# APM9328_PERIPH.net
KiCad netlist of a schematic drawn in Altium Designer
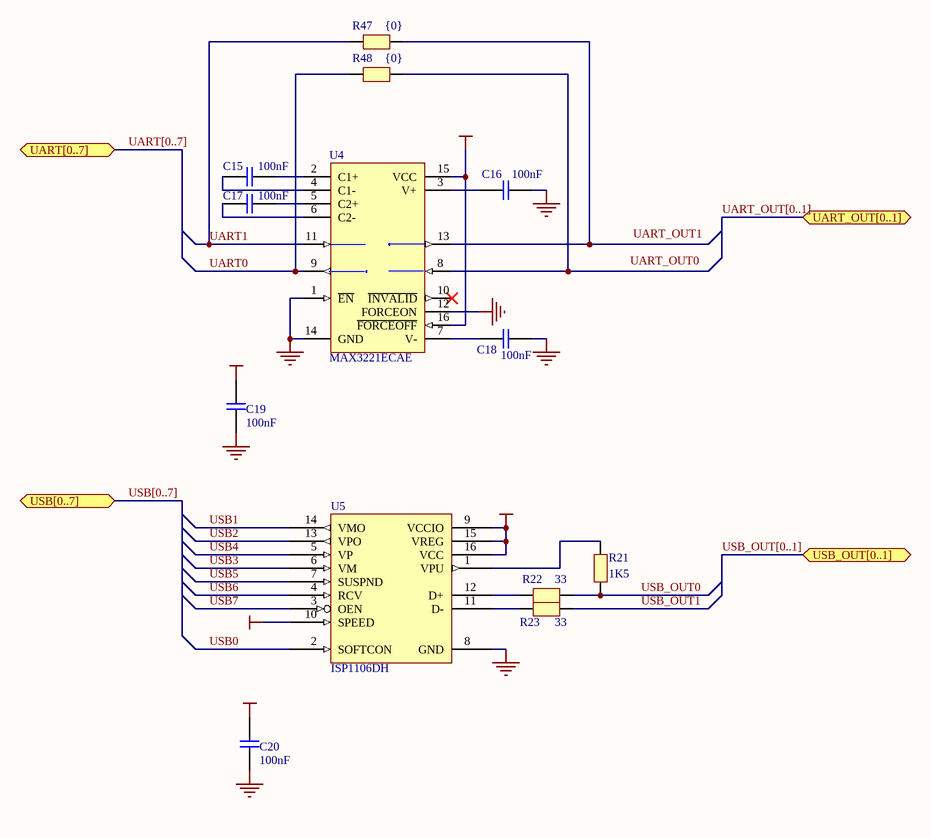
[diagram p0: APM9328_PERIPH.SchDoc]

(export (version "E")
  (design (tool "Eeschema 10.0.6"))
  (components
    (comp (ref "C15") (value "100nF") (footprint "0402") (libsource (lib "Misc") (part "Cap")))
    (comp (ref "C16") (value "100nF") (footprint "0402") (libsource (lib "Misc") (part "Cap")))
    (comp (ref "C17") (value "100nF") (footprint "0402") (libsource (lib "Misc") (part "Cap")))
    (comp (ref "C18") (value "100nF") (footprint "0402") (libsource (lib "Misc") (part "Cap")))
    (comp (ref "C19") (value "100nF") (footprint "0402") (libsource (lib "Misc") (part "Cap")))
    (comp (ref "C20") (value "100nF") (footprint "0402") (libsource (lib "Misc") (part "Cap")))
    (comp (ref "R21") (value "1K5") (footprint "0402") (libsource (lib "") (part "Res_1")))
    (comp (ref "R22") (value "33") (footprint "0402") (libsource (lib "*") (part "Res")))
    (comp (ref "R23") (value "33") (footprint "0402") (libsource (lib "*") (part "Res")))
    (comp (ref "R47") (value "{0}") (footprint "0402") (libsource (lib "*") (part "Res")))
    (comp (ref "R48") (value "{0}") (footprint "0402") (libsource (lib "*") (part "Res")))
    (comp (ref "U4")
      (value "MAX3221ECAE")
      (footprint "TSSOP16")
      (description "±15kV ESD-Protected, 1µA, 3.0V/5.5V, 250kbps, RS-232 Transceiver with AutoShutdown")
      (fields
        (field (name "MANUFACTURER") "Texas Instrument")
        (field (name "PART NUMBER") "MAX3221CPWR")
        (field (name "PUBLISHER") "Altium Limited")
      )
      (libsource (lib "Maxim Communication Transceiver") (part "MAX3221ECAE"))
    )
    (comp (ref "U5")
      (value "ISP1106DH")
      (footprint "TSSOP16")
      (description "USB 1.1 transceiver")
      (fields (field (name "MANUFACTURER") "Philips"))
      (libsource (lib "*") (part "ISP1106"))
    )
  )
  (nets
    (net (code "7") (name "+3V3") (class "Default")
      (node (ref "C19") (pin "1") (pintype "passive"))
      (node (ref "C20") (pin "1") (pintype "passive"))
      (node (ref "U4") (pin "15") (pinfunction "VCC_15") (pintype "power_in"))
      (node (ref "U4") (pin "16") (pinfunction "~{FORCEOFF}_16") (pintype "input"))
      (node (ref "U5") (pin "10") (pinfunction "SPEED_10") (pintype "input"))
      (node (ref "U5") (pin "15") (pinfunction "VREG_15") (pintype "power_in"))
      (node (ref "U5") (pin "16") (pinfunction "VCC_16") (pintype "power_in"))
      (node (ref "U5") (pin "9") (pinfunction "VCCIO_9") (pintype "power_in"))
    )
    (net (code "8") (name "/UART0") (class "Default")
      (node (ref "R48") (pin "1") (pintype "passive"))
      (node (ref "U4") (pin "9") (pinfunction "R1OUT_9") (pintype "output"))
    )
    (net (code "9") (name "/UART1") (class "Default")
      (node (ref "R47") (pin "1") (pintype "passive"))
      (node (ref "U4") (pin "11") (pinfunction "T1IN_11") (pintype "input"))
    )
    (net (code "14") (name "/USB0") (class "Default")
      (node (ref "U5") (pin "2") (pinfunction "SOFTCON_2") (pintype "input"))
    )
    (net (code "15") (name "/USB1") (class "Default")
      (node (ref "U5") (pin "14") (pinfunction "VMO_14") (pintype "output"))
    )
    (net (code "16") (name "/USB2") (class "Default")
      (node (ref "U5") (pin "13") (pinfunction "VPO_13") (pintype "output"))
    )
    (net (code "17") (name "/USB3") (class "Default")
      (node (ref "U5") (pin "6") (pinfunction "VM_6") (pintype "input"))
    )
    (net (code "18") (name "/USB4") (class "Default")
      (node (ref "U5") (pin "5") (pinfunction "VP_5") (pintype "input"))
    )
    (net (code "19") (name "/USB5") (class "Default")
      (node (ref "U5") (pin "7") (pinfunction "SUSPND_7") (pintype "input"))
    )
    (net (code "20") (name "/USB6") (class "Default")
      (node (ref "U5") (pin "4") (pinfunction "RCV_4") (pintype "input"))
    )
    (net (code "21") (name "/USB7") (class "Default")
      (node (ref "U5") (pin "3") (pinfunction "OEN_3") (pintype "input"))
    )
    (net (code "23") (name "/USB_OUT0") (class "Default")
      (node (ref "R21") (pin "1") (pintype "passive"))
      (node (ref "R22") (pin "2") (pintype "passive"))
    )
    (net (code "24") (name "/USB_OUT1") (class "Default") (node (ref "R23") (pin "2") (pintype "passive")))
    (net (code "26") (name "GND") (class "Default")
      (node (ref "C16") (pin "2") (pintype "passive"))
      (node (ref "C18") (pin "2") (pintype "passive"))
      (node (ref "C19") (pin "2") (pintype "passive"))
      (node (ref "C20") (pin "2") (pintype "passive"))
      (node (ref "U4") (pin "1") (pinfunction "~{EN}_1") (pintype "input"))
      (node (ref "U4") (pin "12") (pinfunction "FORCEON_12") (pintype "passive"))
      (node (ref "U4") (pin "14") (pinfunction "GND_14") (pintype "power_in"))
      (node (ref "U5") (pin "8") (pinfunction "GND_8") (pintype "power_in"))
    )
    (net (code "27") (name "Net-(U4-C1+)") (class "Default")
      (node (ref "C15") (pin "2") (pintype "passive"))
      (node (ref "U4") (pin "2") (pinfunction "C1+_2") (pintype "passive"))
    )
    (net (code "28") (name "Net-(U4-C1-)") (class "Default")
      (node (ref "C15") (pin "1") (pintype "passive"))
      (node (ref "U4") (pin "4") (pinfunction "C1-_4") (pintype "passive"))
    )
    (net (code "29") (name "Net-(U4-C2+)") (class "Default")
      (node (ref "C17") (pin "2") (pintype "passive"))
      (node (ref "U4") (pin "5") (pinfunction "C2+_5") (pintype "passive"))
    )
    (net (code "30") (name "Net-(U4-C2-)") (class "Default")
      (node (ref "C17") (pin "1") (pintype "passive"))
      (node (ref "U4") (pin "6") (pinfunction "C2-_6") (pintype "passive"))
    )
    (net (code "31") (name "Net-(U4-R1IN)") (class "Default")
      (node (ref "R48") (pin "2") (pintype "passive"))
      (node (ref "U4") (pin "8") (pinfunction "R1IN_8") (pintype "input"))
    )
    (net (code "32") (name "Net-(U4-T1OUT)") (class "Default")
      (node (ref "R47") (pin "2") (pintype "passive"))
      (node (ref "U4") (pin "13") (pinfunction "T1OUT_13") (pintype "output"))
    )
    (net (code "33") (name "Net-(U4-V+)") (class "Default")
      (node (ref "C16") (pin "1") (pintype "passive"))
      (node (ref "U4") (pin "3") (pinfunction "V+_3") (pintype "power_in"))
    )
    (net (code "34") (name "Net-(U4-V-)") (class "Default")
      (node (ref "C18") (pin "1") (pintype "passive"))
      (node (ref "U4") (pin "7") (pinfunction "V-_7") (pintype "power_in"))
    )
    (net (code "35") (name "Net-(U5-D+)") (class "Default")
      (node (ref "R22") (pin "1") (pintype "passive"))
      (node (ref "U5") (pin "12") (pinfunction "D+_12") (pintype "passive"))
    )
    (net (code "36") (name "Net-(U5-D-)") (class "Default")
      (node (ref "R23") (pin "1") (pintype "passive"))
      (node (ref "U5") (pin "11") (pinfunction "D-_11") (pintype "passive"))
    )
    (net (code "37") (name "Net-(U5-VPU)") (class "Default")
      (node (ref "R21") (pin "2") (pintype "passive"))
      (node (ref "U5") (pin "1") (pinfunction "VPU_1") (pintype "output"))
    )
    (net (code "38") (name "unconnected-(U4-~{INVALID}-Pad10)") (class "Default")
      (node (ref "U4") (pin "10") (pinfunction "~{INVALID}_10") (pintype "output+no_connect"))
    )
  )
)
